# ospi_v10.net
KiCad netlist of a schematic drawn in EAGLE
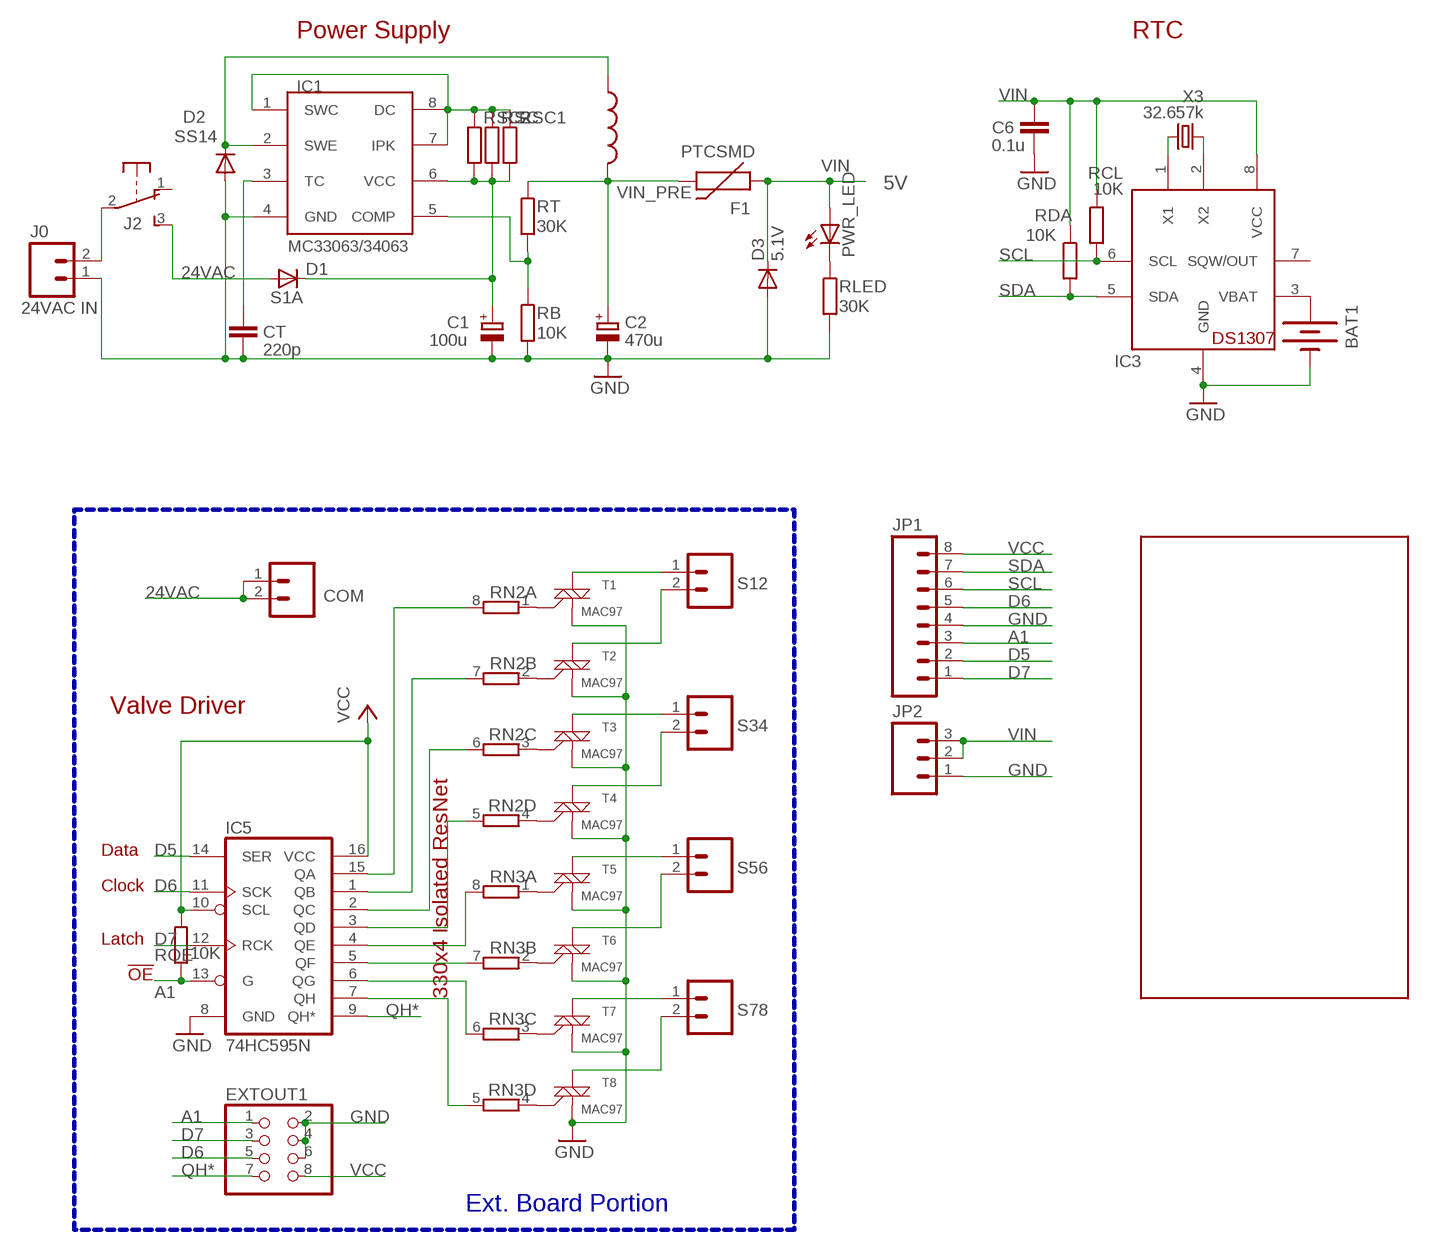
[diagram p0: schematic, sheet 1]

(export (version "E")
  (design (tool "Eeschema 10.0.6"))
  (components
    (comp (ref "BAT1")
      (value "BATTERYBATTERY_12MM_SMT")
      (footprint "eagle-import:BATTCON_12MM_SMT")
      (libsource (lib "eagle-import") (part "BATTERYBATTERY_12MM_SMT"))
    )
    (comp (ref "C1")
      (value "100u")
      (footprint "eagle-import:E3,5-8")
      (libsource (lib "eagle-import") (part "CPOL-EUE3.5-8"))
    )
    (comp (ref "C2")
      (value "470u")
      (footprint "eagle-import:E3,5-8")
      (libsource (lib "eagle-import") (part "CPOL-EUE3.5-8"))
    )
    (comp (ref "C6")
      (value "0.1u")
      (footprint "eagle-import:C0805")
      (libsource (lib "eagle-import") (part "C-EUC0805"))
    )
    (comp (ref "COM")
      (value "M025MM")
      (footprint "eagle-import:SCREWTERMINAL-5MM-2")
      (libsource (lib "eagle-import") (part "M025MM"))
    )
    (comp (ref "CT")
      (value "220p")
      (footprint "eagle-import:C0805")
      (libsource (lib "eagle-import") (part "C-EUC0805"))
    )
    (comp (ref "D1")
      (value "S1A")
      (footprint "eagle-import:DO41-7.6")
      (libsource (lib "eagle-import") (part "DIODE-DO41-7.6"))
    )
    (comp (ref "D2")
      (value "SS14")
      (footprint "eagle-import:DO214AC")
      (libsource (lib "eagle-import") (part "DIODE-DO214AC"))
    )
    (comp (ref "D3")
      (value "5.1V")
      (footprint "eagle-import:DO34-7")
      (libsource (lib "eagle-import") (part "DIODE-DO34-7"))
    )
    (comp (ref "EXTOUT1")
      (value "PINHD-2X4/90")
      (footprint "eagle-import:2X04_90")
      (libsource (lib "eagle-import") (part "PINHD-2X4/90"))
    )
    (comp (ref "F1")
      (value "PTCSMD")
      (footprint "eagle-import:PTC-1206")
      (libsource (lib "eagle-import") (part "PTCSMD"))
    )
    (comp (ref "IC1")
      (value "MC33063/MC34063D")
      (footprint "eagle-import:SO08")
      (libsource (lib "eagle-import") (part "MC33063/MC34063D"))
    )
    (comp (ref "IC3")
      (value "DS1307")
      (footprint "eagle-import:SO08")
      (libsource (lib "eagle-import") (part "DS1307SOIC"))
    )
    (comp (ref "IC5")
      (value "74HC595N")
      (footprint "eagle-import:SO16")
      (libsource (lib "eagle-import") (part "74595DLS"))
    )
    (comp (ref "J0")
      (value "24VAC IN")
      (footprint "eagle-import:SCREWTERMINAL-5MM-2")
      (libsource (lib "eagle-import") (part "M025MM"))
    )
    (comp (ref "J2")
      (value "EG1206")
      (footprint "eagle-import:EG1206")
      (libsource (lib "eagle-import") (part "EG1206"))
    )
    (comp (ref "JP1")
      (value "M08LOCK")
      (footprint "eagle-import:1X08_LOCK")
      (libsource (lib "eagle-import") (part "M08LOCK"))
    )
    (comp (ref "JP2")
      (value "M03LOCK")
      (footprint "eagle-import:1X03_LOCK")
      (libsource (lib "eagle-import") (part "M03LOCK"))
    )
    (comp (ref "L1'")
      (value "220uH")
      (footprint "eagle-import:SRU1038")
      (libsource (lib "eagle-import") (part "INDUCTORSRU1038"))
    )
    (comp (ref "PWR_LED")
      (value "LEDCHIPLED_0805")
      (footprint "eagle-import:CHIPLED_0805")
      (libsource (lib "eagle-import") (part "LEDCHIPLED_0805"))
    )
    (comp (ref "RB")
      (value "10K")
      (footprint "eagle-import:R0805")
      (libsource (lib "eagle-import") (part "R-EU_R0805"))
    )
    (comp (ref "RCL")
      (value "10K")
      (footprint "eagle-import:R0805")
      (libsource (lib "eagle-import") (part "R-EU_R0805"))
    )
    (comp (ref "RDA")
      (value "10K")
      (footprint "eagle-import:R0805")
      (libsource (lib "eagle-import") (part "R-EU_R0805"))
    )
    (comp (ref "RLED")
      (value "30K")
      (footprint "eagle-import:R0805")
      (libsource (lib "eagle-import") (part "R-EU_R0805"))
    )
    (comp (ref "RN2")
      (value "4R-NEXB38V")
      (footprint "eagle-import:EXB38V")
      (libsource (lib "eagle-import") (part "4R-NEXB38V"))
    )
    (comp (ref "RN3")
      (value "4R-NEXB38V")
      (footprint "eagle-import:EXB38V")
      (libsource (lib "eagle-import") (part "4R-NEXB38V"))
    )
    (comp (ref "ROE")
      (value "10K")
      (footprint "eagle-import:R0805")
      (libsource (lib "eagle-import") (part "R-EU_R0805"))
    )
    (comp (ref "RSC")
      (value "1.0")
      (footprint "eagle-import:R0805")
      (libsource (lib "eagle-import") (part "R-EU_R0805"))
    )
    (comp (ref "RSC1")
      (value "1.0")
      (footprint "eagle-import:R0805")
      (libsource (lib "eagle-import") (part "R-EU_R0805"))
    )
    (comp (ref "RSC2")
      (value "1.0")
      (footprint "eagle-import:R0805")
      (libsource (lib "eagle-import") (part "R-EU_R0805"))
    )
    (comp (ref "RT")
      (value "30K")
      (footprint "eagle-import:R0805")
      (libsource (lib "eagle-import") (part "R-EU_R0805"))
    )
    (comp (ref "S12")
      (value "M025MM")
      (footprint "eagle-import:SCREWTERMINAL-5MM-2")
      (libsource (lib "eagle-import") (part "M025MM"))
    )
    (comp (ref "S34")
      (value "M025MM")
      (footprint "eagle-import:SCREWTERMINAL-5MM-2")
      (libsource (lib "eagle-import") (part "M025MM"))
    )
    (comp (ref "S56")
      (value "M025MM")
      (footprint "eagle-import:SCREWTERMINAL-5MM-2")
      (libsource (lib "eagle-import") (part "M025MM"))
    )
    (comp (ref "S78")
      (value "M025MM")
      (footprint "eagle-import:SCREWTERMINAL-5MM-2")
      (libsource (lib "eagle-import") (part "M025MM"))
    )
    (comp (ref "T1")
      (value "MAC97")
      (footprint "eagle-import:SOT223")
      (libsource (lib "eagle-import") (part "MAC97SOT223"))
    )
    (comp (ref "T2")
      (value "MAC97")
      (footprint "eagle-import:SOT223")
      (libsource (lib "eagle-import") (part "MAC97SOT223"))
    )
    (comp (ref "T3")
      (value "MAC97")
      (footprint "eagle-import:SOT223")
      (libsource (lib "eagle-import") (part "MAC97SOT223"))
    )
    (comp (ref "T4")
      (value "MAC97")
      (footprint "eagle-import:SOT223")
      (libsource (lib "eagle-import") (part "MAC97SOT223"))
    )
    (comp (ref "T5")
      (value "MAC97")
      (footprint "eagle-import:SOT223")
      (libsource (lib "eagle-import") (part "MAC97SOT223"))
    )
    (comp (ref "T6")
      (value "MAC97")
      (footprint "eagle-import:SOT223")
      (libsource (lib "eagle-import") (part "MAC97SOT223"))
    )
    (comp (ref "T7")
      (value "MAC97")
      (footprint "eagle-import:SOT223")
      (libsource (lib "eagle-import") (part "MAC97SOT223"))
    )
    (comp (ref "T8")
      (value "MAC97")
      (footprint "eagle-import:SOT223")
      (libsource (lib "eagle-import") (part "MAC97SOT223"))
    )
    (comp (ref "U$2")
      (value "OSPI")
      (footprint "eagle-import:OSPI")
      (libsource (lib "eagle-import") (part "OSPI"))
    )
    (comp (ref "X3")
      (value "32.657k")
      (footprint "eagle-import:TC26H")
      (libsource (lib "eagle-import") (part "CRYSTALTC26H"))
    )
  )
  (nets
    (net (code "1") (name "/24VAC") (class "Default")
      (node (ref "COM") (pin "1") (pinfunction "1_1") (pintype "passive"))
      (node (ref "COM") (pin "2") (pinfunction "2_2") (pintype "passive"))
      (node (ref "D1") (pin "A") (pinfunction "A_A") (pintype "passive"))
      (node (ref "J2") (pin "3") (pinfunction "S_3") (pintype "passive"))
    )
    (net (code "2") (name "/A1") (class "Default")
      (node (ref "EXTOUT1") (pin "1") (pinfunction "1_1") (pintype "passive"))
      (node (ref "IC5") (pin "13") (pinfunction "G_13") (pintype "input"))
      (node (ref "JP1") (pin "3") (pinfunction "3_3") (pintype "passive"))
      (node (ref "ROE") (pin "1") (pinfunction "1_1") (pintype "passive"))
    )
    (net (code "3") (name "/D5") (class "Default")
      (node (ref "IC5") (pin "14") (pinfunction "SER_14") (pintype "input"))
      (node (ref "JP1") (pin "2") (pinfunction "2_2") (pintype "passive"))
    )
    (net (code "4") (name "/D6") (class "Default")
      (node (ref "EXTOUT1") (pin "5") (pinfunction "5_5") (pintype "passive"))
      (node (ref "IC5") (pin "11") (pinfunction "SCK_11") (pintype "input"))
      (node (ref "JP1") (pin "5") (pinfunction "5_5") (pintype "passive"))
    )
    (net (code "5") (name "/D7") (class "Default")
      (node (ref "EXTOUT1") (pin "3") (pinfunction "3_3") (pintype "passive"))
      (node (ref "IC5") (pin "12") (pinfunction "RCK_12") (pintype "input"))
      (node (ref "JP1") (pin "1") (pinfunction "1_1") (pintype "passive"))
    )
    (net (code "6") (name "/QH*") (class "Default")
      (node (ref "EXTOUT1") (pin "7") (pinfunction "7_7") (pintype "passive"))
      (node (ref "IC5") (pin "9") (pinfunction "QH*_9") (pintype "tri_state"))
    )
    (net (code "7") (name "/SCL") (class "Default")
      (node (ref "IC3") (pin "6") (pinfunction "SCL_6") (pintype "bidirectional"))
      (node (ref "JP1") (pin "6") (pinfunction "6_6") (pintype "passive"))
      (node (ref "RCL") (pin "2") (pinfunction "2_2") (pintype "passive"))
    )
    (net (code "8") (name "/SDA") (class "Default")
      (node (ref "IC3") (pin "5") (pinfunction "SDA_5") (pintype "bidirectional"))
      (node (ref "JP1") (pin "7") (pinfunction "7_7") (pintype "passive"))
      (node (ref "RDA") (pin "2") (pinfunction "2_2") (pintype "passive"))
    )
    (net (code "9") (name "/VIN") (class "Default")
      (node (ref "C6") (pin "1") (pinfunction "1_1") (pintype "passive"))
      (node (ref "D3") (pin "C") (pinfunction "C_C") (pintype "passive"))
      (node (ref "F1") (pin "1") (pinfunction "1_1") (pintype "bidirectional"))
      (node (ref "IC3") (pin "8") (pinfunction "VCC_8") (pintype "power_in"))
      (node (ref "JP2") (pin "2") (pinfunction "2_2") (pintype "passive"))
      (node (ref "JP2") (pin "3") (pinfunction "3_3") (pintype "passive"))
      (node (ref "PWR_LED") (pin "A") (pinfunction "A_A") (pintype "passive"))
      (node (ref "RCL") (pin "1") (pinfunction "1_1") (pintype "passive"))
      (node (ref "RDA") (pin "1") (pinfunction "1_1") (pintype "passive"))
    )
    (net (code "10") (name "/VIN_PRE") (class "Default")
      (node (ref "C2") (pin "+") (pinfunction "+_+") (pintype "passive"))
      (node (ref "F1") (pin "2") (pinfunction "2_2") (pintype "bidirectional"))
      (node (ref "L1'") (pin "2") (pinfunction "2_2") (pintype "passive"))
      (node (ref "RT") (pin "1") (pinfunction "1_1") (pintype "passive"))
    )
    (net (code "11") (name "GND") (class "Default")
      (node (ref "BAT1") (pin "P$1") (pinfunction "-_P$1") (pintype "power_in"))
      (node (ref "C1") (pin "-") (pinfunction "-_-") (pintype "passive"))
      (node (ref "C2") (pin "-") (pinfunction "-_-") (pintype "passive"))
      (node (ref "C6") (pin "2") (pinfunction "2_2") (pintype "passive"))
      (node (ref "CT") (pin "2") (pinfunction "2_2") (pintype "passive"))
      (node (ref "D2") (pin "A") (pinfunction "A_A") (pintype "passive"))
      (node (ref "D3") (pin "A") (pinfunction "A_A") (pintype "passive"))
      (node (ref "EXTOUT1") (pin "2") (pinfunction "2_2") (pintype "passive"))
      (node (ref "EXTOUT1") (pin "4") (pinfunction "4_4") (pintype "passive"))
      (node (ref "EXTOUT1") (pin "6") (pinfunction "6_6") (pintype "passive"))
      (node (ref "IC1") (pin "4") (pinfunction "GND_4") (pintype "power_in"))
      (node (ref "IC3") (pin "4") (pinfunction "GND_4") (pintype "power_in"))
      (node (ref "IC5") (pin "8") (pinfunction "GND_8") (pintype "power_in"))
      (node (ref "J0") (pin "1") (pinfunction "1_1") (pintype "passive"))
      (node (ref "JP1") (pin "4") (pinfunction "4_4") (pintype "passive"))
      (node (ref "JP2") (pin "1") (pinfunction "1_1") (pintype "passive"))
      (node (ref "RB") (pin "2") (pinfunction "2_2") (pintype "passive"))
      (node (ref "RLED") (pin "2") (pinfunction "2_2") (pintype "passive"))
      (node (ref "T1") (pin "1") (pinfunction "M1_1") (pintype "bidirectional"))
      (node (ref "T2") (pin "1") (pinfunction "M1_1") (pintype "bidirectional"))
      (node (ref "T3") (pin "1") (pinfunction "M1_1") (pintype "bidirectional"))
      (node (ref "T4") (pin "1") (pinfunction "M1_1") (pintype "bidirectional"))
      (node (ref "T5") (pin "1") (pinfunction "M1_1") (pintype "bidirectional"))
      (node (ref "T6") (pin "1") (pinfunction "M1_1") (pintype "bidirectional"))
      (node (ref "T7") (pin "1") (pinfunction "M1_1") (pintype "bidirectional"))
      (node (ref "T8") (pin "1") (pinfunction "M1_1") (pintype "bidirectional"))
    )
    (net (code "12") (name "Net-(BAT1-+)") (class "Default")
      (node (ref "BAT1") (pin "P$2") (pinfunction "+_P$2") (pintype "power_in"))
      (node (ref "IC3") (pin "3") (pinfunction "VBAT_3") (pintype "power_in"))
    )
    (net (code "13") (name "Net-(IC1-COMP)") (class "Default")
      (node (ref "IC1") (pin "5") (pinfunction "COMP_5") (pintype "input"))
      (node (ref "RB") (pin "1") (pinfunction "1_1") (pintype "passive"))
      (node (ref "RT") (pin "2") (pinfunction "2_2") (pintype "passive"))
    )
    (net (code "14") (name "Net-(IC1-DC)") (class "Default")
      (node (ref "IC1") (pin "1") (pinfunction "SWC_1") (pintype "input"))
      (node (ref "IC1") (pin "7") (pinfunction "IPK_7") (pintype "bidirectional"))
      (node (ref "IC1") (pin "8") (pinfunction "DC_8") (pintype "input"))
      (node (ref "RSC") (pin "1") (pinfunction "1_1") (pintype "passive"))
      (node (ref "RSC1") (pin "1") (pinfunction "1_1") (pintype "passive"))
      (node (ref "RSC2") (pin "1") (pinfunction "1_1") (pintype "passive"))
    )
    (net (code "15") (name "Net-(IC1-SWE)") (class "Default")
      (node (ref "D2") (pin "C") (pinfunction "C_C") (pintype "passive"))
      (node (ref "IC1") (pin "2") (pinfunction "SWE_2") (pintype "input"))
      (node (ref "L1'") (pin "1") (pinfunction "1_1") (pintype "passive"))
    )
    (net (code "16") (name "Net-(IC1-TC)") (class "Default")
      (node (ref "CT") (pin "1") (pinfunction "1_1") (pintype "passive"))
      (node (ref "IC1") (pin "3") (pinfunction "TC_3") (pintype "input"))
    )
    (net (code "17") (name "Net-(IC1-VCC)") (class "Default")
      (node (ref "C1") (pin "+") (pinfunction "+_+") (pintype "passive"))
      (node (ref "D1") (pin "C") (pinfunction "C_C") (pintype "passive"))
      (node (ref "IC1") (pin "6") (pinfunction "VCC_6") (pintype "power_in"))
      (node (ref "RSC") (pin "2") (pinfunction "2_2") (pintype "passive"))
      (node (ref "RSC1") (pin "2") (pinfunction "2_2") (pintype "passive"))
      (node (ref "RSC2") (pin "2") (pinfunction "2_2") (pintype "passive"))
    )
    (net (code "18") (name "Net-(IC3-X1)") (class "Default")
      (node (ref "IC3") (pin "1") (pinfunction "X1_1") (pintype "passive"))
      (node (ref "X3") (pin "1") (pinfunction "1_1") (pintype "passive"))
    )
    (net (code "19") (name "Net-(IC3-X2)") (class "Default")
      (node (ref "IC3") (pin "2") (pinfunction "X2_2") (pintype "passive"))
      (node (ref "X3") (pin "2") (pinfunction "2_2") (pintype "passive"))
    )
    (net (code "20") (name "Net-(IC5-QA)") (class "Default")
      (node (ref "IC5") (pin "15") (pinfunction "QA_15") (pintype "tri_state"))
      (node (ref "RN2") (pin "8") (pinfunction "2_8") (pintype "passive"))
    )
    (net (code "21") (name "Net-(IC5-QB)") (class "Default")
      (node (ref "IC5") (pin "1") (pinfunction "QB_1") (pintype "tri_state"))
      (node (ref "RN2") (pin "7") (pinfunction "2_7") (pintype "passive"))
    )
    (net (code "22") (name "Net-(IC5-QC)") (class "Default")
      (node (ref "IC5") (pin "2") (pinfunction "QC_2") (pintype "tri_state"))
      (node (ref "RN2") (pin "6") (pinfunction "2_6") (pintype "passive"))
    )
    (net (code "23") (name "Net-(IC5-QD)") (class "Default")
      (node (ref "IC5") (pin "3") (pinfunction "QD_3") (pintype "tri_state"))
      (node (ref "RN2") (pin "5") (pinfunction "2_5") (pintype "passive"))
    )
    (net (code "24") (name "Net-(IC5-QE)") (class "Default")
      (node (ref "IC5") (pin "4") (pinfunction "QE_4") (pintype "tri_state"))
      (node (ref "RN3") (pin "8") (pinfunction "2_8") (pintype "passive"))
    )
    (net (code "25") (name "Net-(IC5-QF)") (class "Default")
      (node (ref "IC5") (pin "5") (pinfunction "QF_5") (pintype "tri_state"))
      (node (ref "RN3") (pin "7") (pinfunction "2_7") (pintype "passive"))
    )
    (net (code "26") (name "Net-(IC5-QG)") (class "Default")
      (node (ref "IC5") (pin "6") (pinfunction "QG_6") (pintype "tri_state"))
      (node (ref "RN3") (pin "6") (pinfunction "2_6") (pintype "passive"))
    )
    (net (code "27") (name "Net-(IC5-QH)") (class "Default")
      (node (ref "IC5") (pin "7") (pinfunction "QH_7") (pintype "tri_state"))
      (node (ref "RN3") (pin "5") (pinfunction "2_5") (pintype "passive"))
    )
    (net (code "28") (name "Net-(J2-P)") (class "Default")
      (node (ref "J0") (pin "2") (pinfunction "2_2") (pintype "passive"))
      (node (ref "J2") (pin "2") (pinfunction "P_2") (pintype "passive"))
    )
    (net (code "29") (name "Net-(PWR_LED-PadC)") (class "Default")
      (node (ref "PWR_LED") (pin "C") (pinfunction "C_C") (pintype "passive"))
      (node (ref "RLED") (pin "1") (pinfunction "1_1") (pintype "passive"))
    )
    (net (code "30") (name "Net-(RN2B-1)") (class "Default")
      (node (ref "RN2") (pin "2") (pinfunction "1_2") (pintype "passive"))
      (node (ref "T2") (pin "3") (pinfunction "G_3") (pintype "bidirectional"))
    )
    (net (code "31") (name "Net-(RN2C-1)") (class "Default")
      (node (ref "RN2") (pin "3") (pinfunction "1_3") (pintype "passive"))
      (node (ref "T3") (pin "3") (pinfunction "G_3") (pintype "bidirectional"))
    )
    (net (code "32") (name "Net-(RN2D-1)") (class "Default")
      (node (ref "RN2") (pin "4") (pinfunction "1_4") (pintype "passive"))
      (node (ref "T4") (pin "3") (pinfunction "G_3") (pintype "bidirectional"))
    )
    (net (code "33") (name "Net-(RN3B-1)") (class "Default")
      (node (ref "RN3") (pin "2") (pinfunction "1_2") (pintype "passive"))
      (node (ref "T6") (pin "3") (pinfunction "G_3") (pintype "bidirectional"))
    )
    (net (code "34") (name "Net-(RN3C-1)") (class "Default")
      (node (ref "RN3") (pin "3") (pinfunction "1_3") (pintype "passive"))
      (node (ref "T7") (pin "3") (pinfunction "G_3") (pintype "bidirectional"))
    )
    (net (code "35") (name "Net-(RN3D-1)") (class "Default")
      (node (ref "RN3") (pin "4") (pinfunction "1_4") (pintype "passive"))
      (node (ref "T8") (pin "3") (pinfunction "G_3") (pintype "bidirectional"))
    )
    (net (code "36") (name "Net-(T1-G)") (class "Default")
      (node (ref "RN2") (pin "1") (pinfunction "1_1") (pintype "passive"))
      (node (ref "T1") (pin "3") (pinfunction "G_3") (pintype "bidirectional"))
    )
    (net (code "37") (name "Net-(T1-M2)") (class "Default")
      (node (ref "S12") (pin "1") (pinfunction "1_1") (pintype "passive"))
      (node (ref "T1") (pin "4") (pinfunction "M2_4") (pintype "bidirectional"))
    )
    (net (code "38") (name "Net-(T2-M2)") (class "Default")
      (node (ref "S12") (pin "2") (pinfunction "2_2") (pintype "passive"))
      (node (ref "T2") (pin "4") (pinfunction "M2_4") (pintype "bidirectional"))
    )
    (net (code "39") (name "Net-(T3-M2)") (class "Default")
      (node (ref "S34") (pin "1") (pinfunction "1_1") (pintype "passive"))
      (node (ref "T3") (pin "4") (pinfunction "M2_4") (pintype "bidirectional"))
    )
    (net (code "40") (name "Net-(T4-M2)") (class "Default")
      (node (ref "S34") (pin "2") (pinfunction "2_2") (pintype "passive"))
      (node (ref "T4") (pin "4") (pinfunction "M2_4") (pintype "bidirectional"))
    )
    (net (code "41") (name "Net-(T5-G)") (class "Default")
      (node (ref "RN3") (pin "1") (pinfunction "1_1") (pintype "passive"))
      (node (ref "T5") (pin "3") (pinfunction "G_3") (pintype "bidirectional"))
    )
    (net (code "42") (name "Net-(T5-M2)") (class "Default")
      (node (ref "S56") (pin "1") (pinfunction "1_1") (pintype "passive"))
      (node (ref "T5") (pin "4") (pinfunction "M2_4") (pintype "bidirectional"))
    )
    (net (code "43") (name "Net-(T6-M2)") (class "Default")
      (node (ref "S56") (pin "2") (pinfunction "2_2") (pintype "passive"))
      (node (ref "T6") (pin "4") (pinfunction "M2_4") (pintype "bidirectional"))
    )
    (net (code "44") (name "Net-(T7-M2)") (class "Default")
      (node (ref "S78") (pin "1") (pinfunction "1_1") (pintype "passive"))
      (node (ref "T7") (pin "4") (pinfunction "M2_4") (pintype "bidirectional"))
    )
    (net (code "45") (name "Net-(T8-M2)") (class "Default")
      (node (ref "S78") (pin "2") (pinfunction "2_2") (pintype "passive"))
      (node (ref "T8") (pin "4") (pinfunction "M2_4") (pintype "bidirectional"))
    )
    (net (code "46") (name "VCC") (class "Default")
      (node (ref "EXTOUT1") (pin "8") (pinfunction "8_8") (pintype "passive"))
      (node (ref "IC5") (pin "10") (pinfunction "SCL_10") (pintype "input"))
      (node (ref "IC5") (pin "16") (pinfunction "VCC_16") (pintype "power_in"))
      (node (ref "JP1") (pin "8") (pinfunction "8_8") (pintype "passive"))
      (node (ref "ROE") (pin "2") (pinfunction "2_2") (pintype "passive"))
    )
    (net (code "47") (name "unconnected-(IC3-SQW{slash}OUT-Pad7)") (class "Default")
      (node (ref "IC3") (pin "7") (pinfunction "SQW/OUT_7") (pintype "bidirectional"))
    )
    (net (code "48") (name "unconnected-(J2-O-Pad1)") (class "Default")
      (node (ref "J2") (pin "1") (pinfunction "O_1") (pintype "passive"))
    )
  )
)
